# DRV8701EVM_SCHEMATIC.net
KiCad netlist of a schematic drawn in Altium Designer
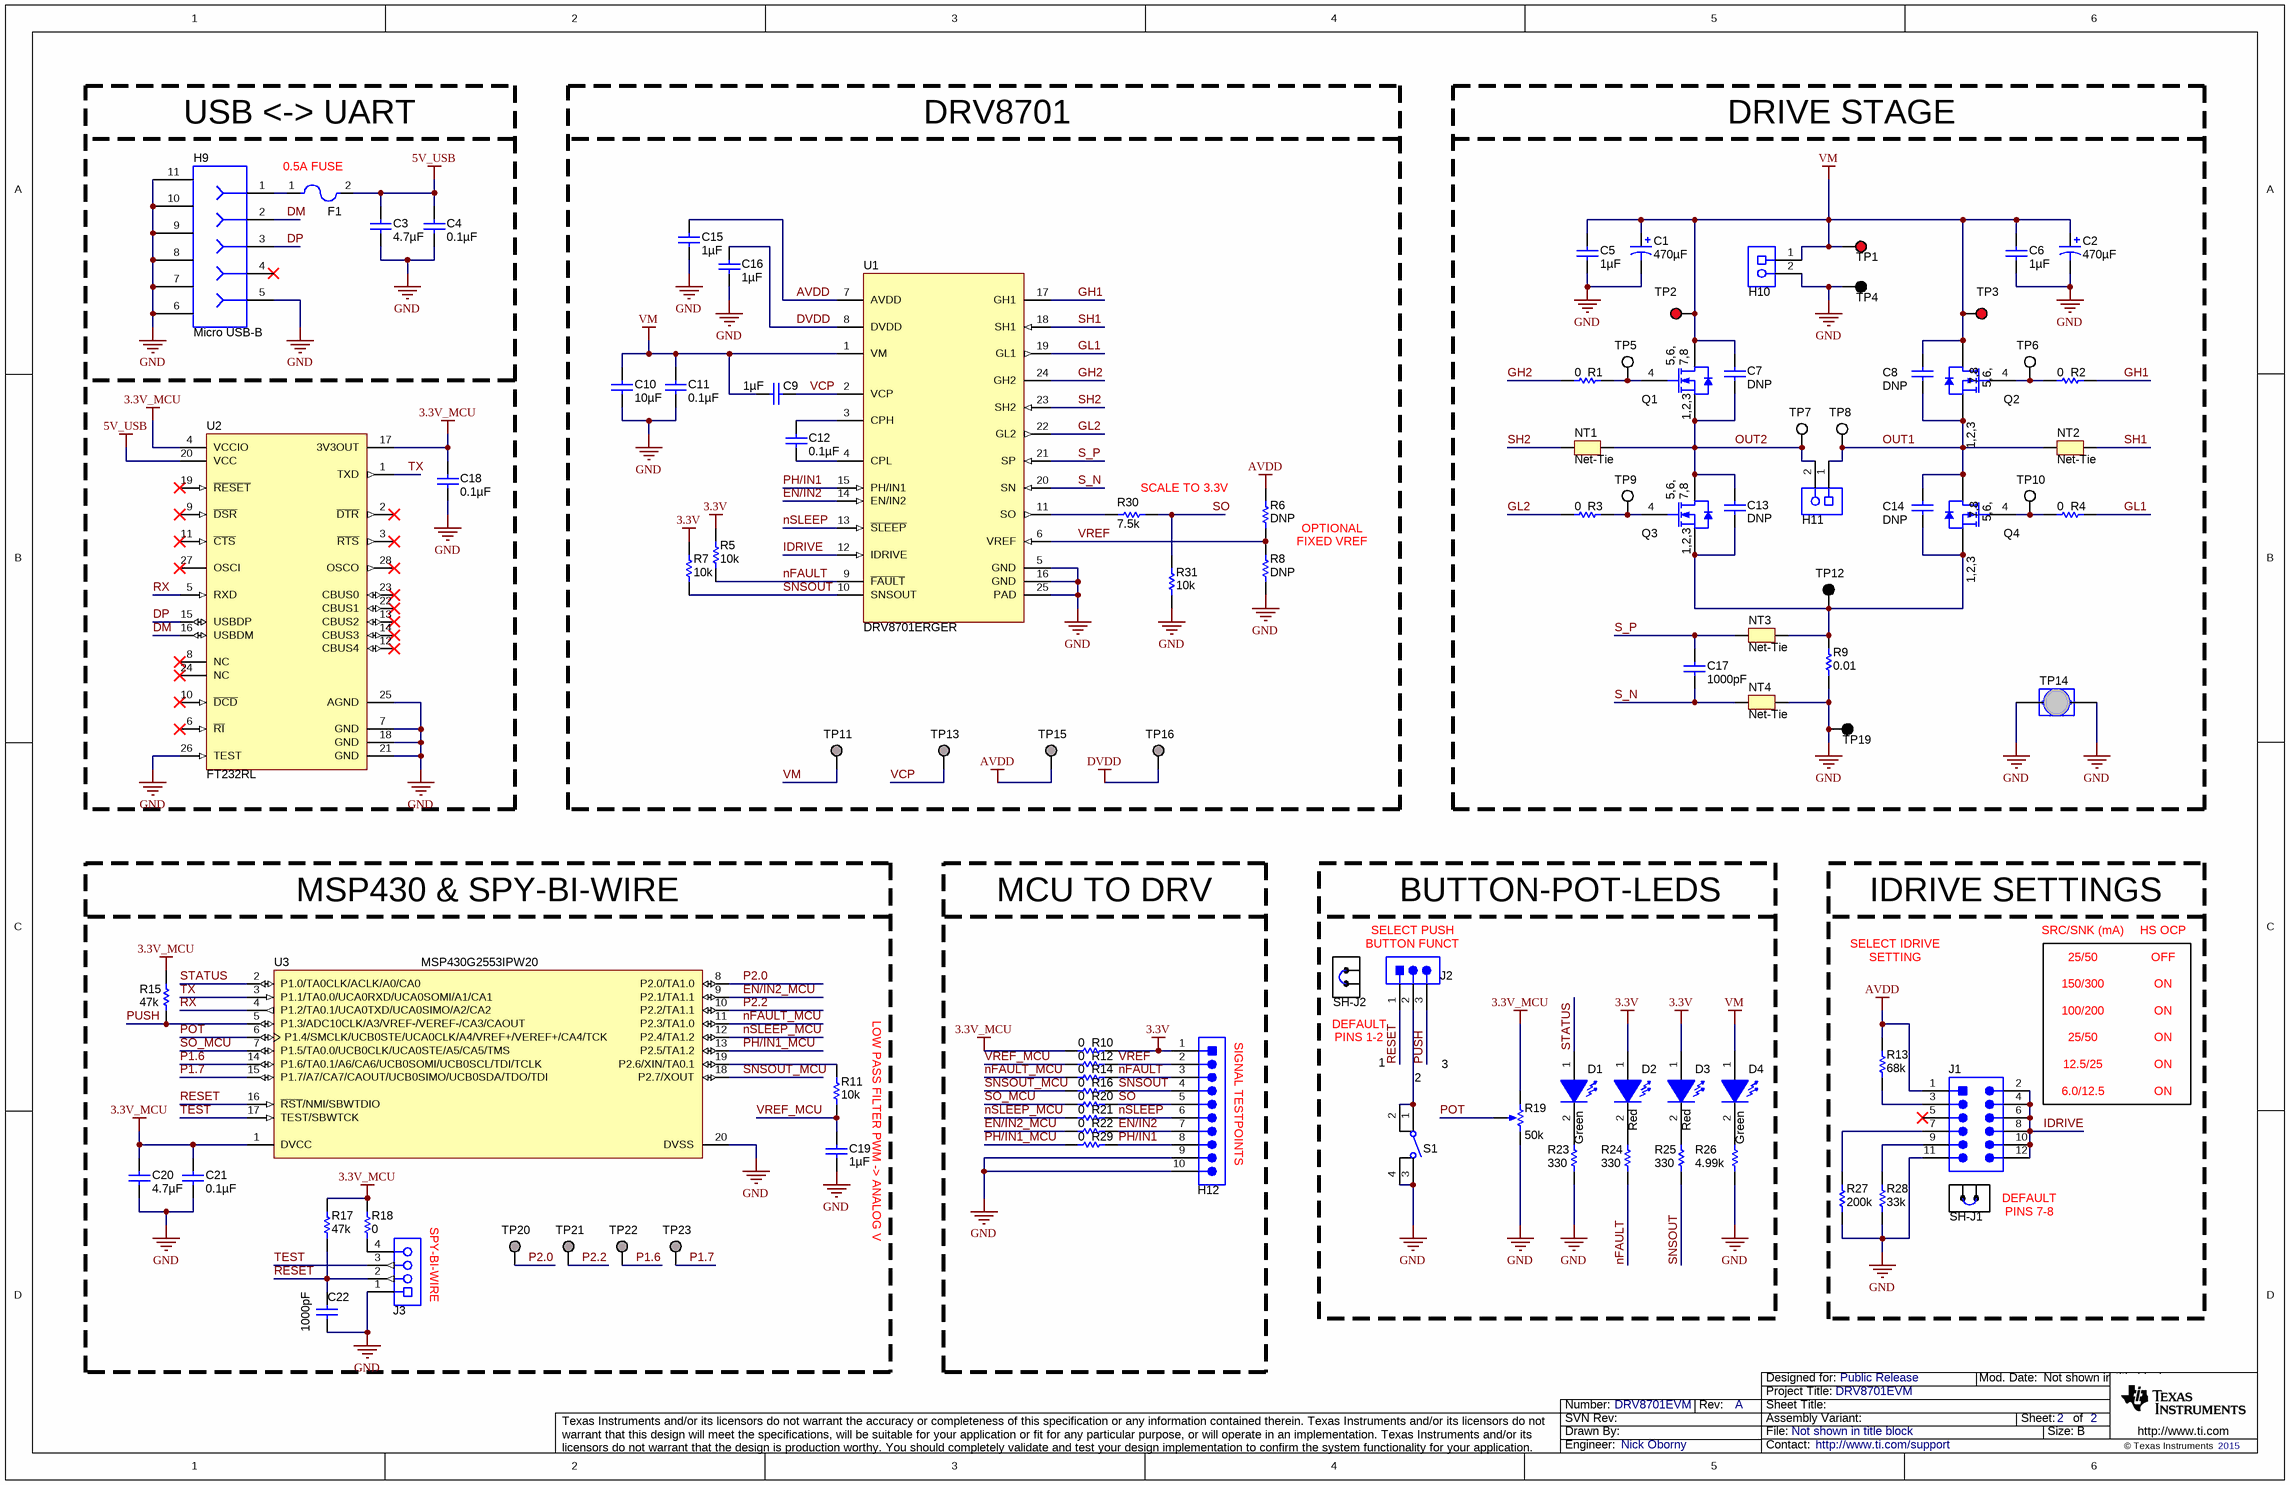
[diagram p0: DRV8701EVM_SCHEMATIC.SchDoc]

(export (version "E")
  (design (tool "Eeschema 10.0.6"))
  (components
    (comp (ref "C1")
      (value "ECA-1HM471")
      (footprint "M_1000x2000")
      (description "CAP, AL, 470 µF, 50 V, +/- 20%,  ohm, TH")
      (fields (field (name "VALUEDISPLAYED") "470µF") (field (name "MANUFACTURER") "Panasonic"))
      (libsource (lib "Capacitor_Aluminum") (part "ECA-1HM471"))
    )
    (comp (ref "C2")
      (value "ECA-1HM471")
      (footprint "M_1000x2000")
      (description "CAP, AL, 470 µF, 50 V, +/- 20%,  ohm, TH")
      (fields (field (name "VALUEDISPLAYED") "470µF") (field (name "MANUFACTURER") "Panasonic"))
      (libsource (lib "Capacitor_Aluminum") (part "ECA-1HM471"))
    )
    (comp (ref "C3")
      (value "C2012X7R1A475M")
      (footprint "0805L")
      (description "CAP, CERM, 4.7uF, 10V, +/-20%, X7R, 0805")
      (fields (field (name "VALUEDISPLAYED") "4.7µF") (field (name "MANUFACTURER") "TDK"))
      (libsource (lib "Capacitor_Ceramic") (part "C2012X7R1A475M"))
    )
    (comp (ref "C4")
      (value "C0603C104K8RACTU")
      (footprint "0603L")
      (description "CAP, CERM, 0.1uF, 10V, +/-10%, X7R, 0603")
      (fields (field (name "VALUEDISPLAYED") "0.1µF") (field (name "MANUFACTURER") "Kemet"))
      (libsource (lib "Capacitor_Ceramic") (part "C0603C104K8RACTU"))
    )
    (comp (ref "C5")
      (value "GRM21BR71H105KA12L")
      (footprint "0805L")
      (description "CAP, CERM, 1uF, 50V, +/-10%, X7R, 0805")
      (fields (field (name "VALUEDISPLAYED") "1µF") (field (name "MANUFACTURER") "MuRata"))
      (libsource (lib "Capacitor_Ceramic") (part "GRM21BR71H105KA12L"))
    )
    (comp (ref "C6")
      (value "GRM21BR71H105KA12L")
      (footprint "0805L")
      (description "CAP, CERM, 1uF, 50V, +/-10%, X7R, 0805")
      (fields (field (name "VALUEDISPLAYED") "1µF") (field (name "MANUFACTURER") "MuRata"))
      (libsource (lib "Capacitor_Ceramic") (part "GRM21BR71H105KA12L"))
    )
    (comp (ref "C7")
      (value "DNP")
      (footprint "0603L")
      (description "CAP, CERM, 0.01uF, 50V, +/-10%, X7R, 0603")
      (fields (field (name "VALUEDISPLAYED") "DNP"))
      (libsource (lib "Capacitor_Ceramic") (part "C1608X7R1H103K"))
    )
    (comp (ref "C8")
      (value "DNP")
      (footprint "0603L")
      (description "CAP, CERM, 0.01uF, 50V, +/-10%, X7R, 0603")
      (fields (field (name "VALUEDISPLAYED") "DNP"))
      (libsource (lib "Capacitor_Ceramic") (part "C1608X7R1H103K"))
    )
    (comp (ref "C9")
      (value "C1608X7R1C105K")
      (footprint "0603L")
      (description "CAP, CERM, 1uF, 16V, +/-10%, X7R, 0603")
      (fields (field (name "VALUEDISPLAYED") "1µF") (field (name "MANUFACTURER") "TDK"))
      (libsource (lib "Capacitor_Ceramic") (part "C1608X7R1C105K"))
    )
    (comp (ref "C10")
      (value "GRM32ER71H106KA12L")
      (footprint "1210L")
      (description "CAP, CERM, 10uF, 50V, +/-10%, X7R, 1210")
      (fields (field (name "VALUEDISPLAYED") "10µF") (field (name "MANUFACTURER") "MuRata"))
      (libsource (lib "Capacitor_Ceramic") (part "GRM32ER71H106KA12L"))
    )
    (comp (ref "C11")
      (value "C1608X7R1H104K")
      (footprint "0603L")
      (description "CAP, CERM, 0.1uF, 50V, +/-10%, X7R, 0603")
      (fields (field (name "VALUEDISPLAYED") "0.1µF") (field (name "MANUFACTURER") "TDK"))
      (libsource (lib "Capacitor_Ceramic") (part "C1608X7R1H104K"))
    )
    (comp (ref "C12")
      (value "C1608X7R1H104K")
      (footprint "0603L")
      (description "CAP, CERM, 0.1uF, 50V, +/-10%, X7R, 0603")
      (fields (field (name "VALUEDISPLAYED") "0.1µF") (field (name "MANUFACTURER") "TDK"))
      (libsource (lib "Capacitor_Ceramic") (part "C1608X7R1H104K"))
    )
    (comp (ref "C13")
      (value "DNP")
      (footprint "0603L")
      (description "CAP, CERM, 0.01uF, 50V, +/-10%, X7R, 0603")
      (fields (field (name "VALUEDISPLAYED") "DNP"))
      (libsource (lib "Capacitor_Ceramic") (part "C1608X7R1H103K"))
    )
    (comp (ref "C14")
      (value "DNP")
      (footprint "0603L")
      (description "CAP, CERM, 0.01uF, 50V, +/-10%, X7R, 0603")
      (fields (field (name "VALUEDISPLAYED") "DNP"))
      (libsource (lib "Capacitor_Ceramic") (part "C1608X7R1H103K"))
    )
    (comp (ref "C15")
      (value "GRM188R70J105KA01D")
      (footprint "0603L")
      (description "CAP, CERM, 1uF, 6.3V, +/-10%, X7R, 0603")
      (fields (field (name "VALUEDISPLAYED") "1µF") (field (name "MANUFACTURER") "MuRata"))
      (libsource (lib "Capacitor_Ceramic") (part "GRM188R70J105KA01D"))
    )
    (comp (ref "C16")
      (value "GRM188R70J105KA01D")
      (footprint "0603L")
      (description "CAP, CERM, 1uF, 6.3V, +/-10%, X7R, 0603")
      (fields (field (name "VALUEDISPLAYED") "1µF") (field (name "MANUFACTURER") "MuRata"))
      (libsource (lib "Capacitor_Ceramic") (part "GRM188R70J105KA01D"))
    )
    (comp (ref "C17")
      (value "GRM155R71C102KA01D")
      (footprint "0402L")
      (description "CAP, CERM, 1000pF, 16V, +/-10%, X7R, 0402")
      (fields (field (name "VALUEDISPLAYED") "1000pF") (field (name "MANUFACTURER") "MuRata"))
      (libsource (lib "Capacitor_Ceramic") (part "GRM155R71C102KA01D"))
    )
    (comp (ref "C18")
      (value "C0603C104K8RACTU")
      (footprint "0603L")
      (description "CAP, CERM, 0.1uF, 10V, +/-10%, X7R, 0603")
      (fields (field (name "VALUEDISPLAYED") "0.1µF") (field (name "MANUFACTURER") "Kemet"))
      (libsource (lib "Capacitor_Ceramic") (part "C0603C104K8RACTU"))
    )
    (comp (ref "C19")
      (value "GRM188R70J105KA01D")
      (footprint "0603L")
      (description "CAP, CERM, 1uF, 6.3V, +/-10%, X7R, 0603")
      (fields (field (name "VALUEDISPLAYED") "1µF") (field (name "MANUFACTURER") "MuRata"))
      (libsource (lib "Capacitor_Ceramic") (part "GRM188R70J105KA01D"))
    )
    (comp (ref "C20")
      (value "C2012X7R1A475M")
      (footprint "0805L")
      (description "CAP, CERM, 4.7uF, 10V, +/-20%, X7R, 0805")
      (fields (field (name "VALUEDISPLAYED") "4.7µF") (field (name "MANUFACTURER") "TDK"))
      (libsource (lib "Capacitor_Ceramic") (part "C2012X7R1A475M"))
    )
    (comp (ref "C21")
      (value "C0603C104K8RACTU")
      (footprint "0603L")
      (description "CAP, CERM, 0.1uF, 10V, +/-10%, X7R, 0603")
      (fields (field (name "VALUEDISPLAYED") "0.1µF") (field (name "MANUFACTURER") "Kemet"))
      (libsource (lib "Capacitor_Ceramic") (part "C0603C104K8RACTU"))
    )
    (comp (ref "C22")
      (value "GRM188R71C102KA01D")
      (footprint "0603L")
      (description "CAP, CERM, 1000pF, 16V, +/-10%, X7R, 0603")
      (fields (field (name "VALUEDISPLAYED") "1000pF") (field (name "MANUFACTURER") "MuRata"))
      (libsource (lib "Capacitor_Ceramic") (part "GRM188R71C102KA01D"))
    )
    (comp (ref "D1")
      (value "Green")
      (footprint "LED_LTST-C171")
      (description "LED, Green, SMD")
      (fields (field (name "MANUFACTURER") "Lite-On") (field (name "PARTNUMBER") "LTST-C171GKT"))
      (libsource (lib "LED") (part "LTST-C171GKT"))
    )
    (comp (ref "D2")
      (value "Red")
      (footprint "LED_LTST-C170")
      (description "LED, Red, SMD")
      (fields (field (name "MANUFACTURER") "Lite-On") (field (name "PARTNUMBER") "LTST-C170KRKT"))
      (libsource (lib "LED") (part "LTST-C170KRKT"))
    )
    (comp (ref "D3")
      (value "Red")
      (footprint "LED_LTST-C170")
      (description "LED, Red, SMD")
      (fields (field (name "MANUFACTURER") "Lite-On") (field (name "PARTNUMBER") "LTST-C170KRKT"))
      (libsource (lib "LED") (part "LTST-C170KRKT"))
    )
    (comp (ref "D4")
      (value "Green")
      (footprint "LED_LTST-C171")
      (description "LED, Green, SMD")
      (fields (field (name "MANUFACTURER") "Lite-On") (field (name "PARTNUMBER") "LTST-C171GKT"))
      (libsource (lib "LED") (part "LTST-C171GKT"))
    )
    (comp (ref "F1")
      (value "1206L050/15YR")
      (footprint "1206_FUSE")
      (description "Fuse, Poly Resetable PTC, 0.5A")
      (fields (field (name "MANUFACTURER") "Littelfuse"))
      (libsource (lib "PADSlegacy_Passive") (part "FUSE_1206L_SERIES"))
    )
    (comp (ref "H9")
      (value "ZX62-B-5PA(11)")
      (footprint "CONN_USB_micro_ZX62-B-5PA")
      (description "Connector, micro USB Type B, Receptacle, R/A, SMD")
      (fields
        (field (name "MANUFACTURER") "Hirose Electric Co. Ltd.")
        (field (name "PACKAGEREFERENCE") "Micro USB-B")
      )
      (libsource (lib "Connectors") (part "ZX62-B-5PA(11)"))
    )
    (comp (ref "H10")
      (value "691 101 710 002")
      (footprint "Wurth_691101710002")
      (description "Terminal Block, 5 mm, 2x1, Tin, TH")
      (fields (field (name "MANUFACTURER") "Wurth Elektronik eiSos"))
      (libsource (lib "Connectors_Other") (part "691 101 710 002"))
    )
    (comp (ref "H11")
      (value "691 101 710 002")
      (footprint "Wurth_691101710002")
      (description "Terminal Block, 5 mm, 2x1, Tin, TH")
      (fields (field (name "MANUFACTURER") "Wurth Elektronik eiSos"))
      (libsource (lib "Connectors_Other") (part "691 101 710 002"))
    )
    (comp (ref "H12")
      (value "TSW-110-07-G-S")
      (footprint "TSW-110-07-G-S")
      (description "Header, 100mil, 10x1, Gold, TH")
      (fields (field (name "MANUFACTURER") "Samtec"))
      (libsource (lib "Connectors_Samtec") (part "TSW-110-07-G-S"))
    )
    (comp (ref "J1")
      (value "PEC06DAAN")
      (footprint "CONN_PEC06DAAN")
      (description "Header, 100mil, 6x2, Tin, TH")
      (fields (field (name "MANUFACTURER") "Sullins Connector Solutions"))
      (libsource (lib "Connectors_Sullins") (part "PEC06DAAN"))
    )
    (comp (ref "J2")
      (value "PEC03SAAN")
      (footprint "CONN_PEC03SAAN")
      (description "Header, 100mil, 3x1, Tin, TH")
      (fields (field (name "MANUFACTURER") "Sullins Connector Solutions"))
      (libsource (lib "Connectors_Sullins") (part "PEC03SAAN"))
    )
    (comp (ref "J3")
      (value "851-43-004-20-001000")
      (footprint "CONN_851-43-004-20-001000")
      (description "SOCKET .050\" GRID SIP 4 POS R/A, TH")
      (fields (field (name "MANUFACTURER") "Mill-Max"))
      (libsource (lib "Connectors") (part "851-43-004-20-001000"))
    )
    (comp (ref "NT1")
      (value "Net-Tie")
      (footprint "Net-Tie_10mil")
      (description "Single point connection between nets.")
      (libsource (lib "") (part "Net-Tie_1"))
    )
    (comp (ref "NT2")
      (value "Net-Tie")
      (footprint "Net-Tie_10mil")
      (description "Single point connection between nets.")
      (libsource (lib "MiscParts") (part "Net-Tie"))
    )
    (comp (ref "NT3")
      (value "Net-Tie")
      (footprint "Net-Tie_10mil")
      (description "Single point connection between nets.")
      (libsource (lib "MiscParts") (part "Net-Tie"))
    )
    (comp (ref "NT4")
      (value "Net-Tie")
      (footprint "Net-Tie_10mil")
      (description "Single point connection between nets.")
      (libsource (lib "") (part "Net-Tie_1"))
    )
    (comp (ref "Q1")
      (value "CSD18532Q5B")
      (footprint "TRANS_NexFET_Q5B")
      (description "MOSFET, N-CH, 60V, 172A, SON 5x6mm")
      (fields (field (name "MANUFACTURER") "Texas Instruments"))
      (libsource (lib "FETs") (part "CSD18532Q5B"))
    )
    (comp (ref "Q2")
      (value "CSD18532Q5B")
      (footprint "TRANS_NexFET_Q5B")
      (description "MOSFET, N-CH, 60V, 172A, SON 5x6mm")
      (fields (field (name "MANUFACTURER") "Texas Instruments"))
      (libsource (lib "FETs") (part "CSD18532Q5B"))
    )
    (comp (ref "Q3")
      (value "CSD18532Q5B")
      (footprint "TRANS_NexFET_Q5B")
      (description "MOSFET, N-CH, 60V, 172A, SON 5x6mm")
      (fields (field (name "MANUFACTURER") "Texas Instruments"))
      (libsource (lib "FETs") (part "CSD18532Q5B"))
    )
    (comp (ref "Q4")
      (value "CSD18532Q5B")
      (footprint "TRANS_NexFET_Q5B")
      (description "MOSFET, N-CH, 60V, 172A, SON 5x6mm")
      (fields (field (name "MANUFACTURER") "Texas Instruments"))
      (libsource (lib "FETs") (part "CSD18532Q5B"))
    )
    (comp (ref "R1")
      (value "0")
      (footprint "0603L")
      (description "RES, 0 ohm, 5%, 0.1W, 0603")
      (fields (field (name "PARTNUMBER") "CRCW06030000Z0EA") (field (name "MANUFACTURER") "Vishay-Dale"))
      (libsource (lib "Resistor_0603") (part "CRCW06030000Z0EA"))
    )
    (comp (ref "R2")
      (value "0")
      (footprint "0603L")
      (description "RES, 0 ohm, 5%, 0.1W, 0603")
      (fields (field (name "PARTNUMBER") "CRCW06030000Z0EA") (field (name "MANUFACTURER") "Vishay-Dale"))
      (libsource (lib "Resistor_0603") (part "CRCW06030000Z0EA"))
    )
    (comp (ref "R3")
      (value "0")
      (footprint "0603L")
      (description "RES, 0 ohm, 5%, 0.1W, 0603")
      (fields (field (name "PARTNUMBER") "CRCW06030000Z0EA") (field (name "MANUFACTURER") "Vishay-Dale"))
      (libsource (lib "Resistor_0603") (part "CRCW06030000Z0EA"))
    )
    (comp (ref "R4")
      (value "0")
      (footprint "0603L")
      (description "RES, 0 ohm, 5%, 0.1W, 0603")
      (fields (field (name "PARTNUMBER") "CRCW06030000Z0EA") (field (name "MANUFACTURER") "Vishay-Dale"))
      (libsource (lib "Resistor_0603") (part "CRCW06030000Z0EA"))
    )
    (comp (ref "R5")
      (value "10k")
      (footprint "0603L")
      (description "RES, 10k ohm, 5%, 0.1W, 0603")
      (fields (field (name "PARTNUMBER") "CRCW060310K0JNEA") (field (name "MANUFACTURER") "Vishay-Dale"))
      (libsource (lib "Resistor_0603") (part "CRCW060310K0JNEA"))
    )
    (comp (ref "R6")
      (value "DNP")
      (footprint "0603L")
      (description "RES, 0 ohm, 5%, 0.1W, 0603")
      (libsource (lib "Resistor_0603") (part "CRCW06030000Z0EA"))
    )
    (comp (ref "R7")
      (value "10k")
      (footprint "0603L")
      (description "RES, 10k ohm, 5%, 0.1W, 0603")
      (fields (field (name "PARTNUMBER") "CRCW060310K0JNEA") (field (name "MANUFACTURER") "Vishay-Dale"))
      (libsource (lib "Resistor_0603") (part "CRCW060310K0JNEA"))
    )
    (comp (ref "R8")
      (value "DNP")
      (footprint "0603L")
      (description "RES, 0 ohm, 5%, 0.1W, 0603")
      (libsource (lib "Resistor_0603") (part "CRCW06030000Z0EA"))
    )
    (comp (ref "R9")
      (value "0.01")
      (footprint "2512M")
      (description "RES, 0.01 ohm, 1%, 3W, 2512")
      (fields (field (name "PARTNUMBER") "CRA2512-FZ-R010ELF") (field (name "MANUFACTURER") "Bourns"))
      (libsource (lib "Resistor_OtherSMT") (part "CRA2512-FZ-R010ELF"))
    )
    (comp (ref "R10")
      (value "0")
      (footprint "0603L")
      (description "RES, 0 ohm, 5%, 0.1W, 0603")
      (fields (field (name "PARTNUMBER") "CRCW06030000Z0EA") (field (name "MANUFACTURER") "Vishay-Dale"))
      (libsource (lib "Resistor_0603") (part "CRCW06030000Z0EA"))
    )
    (comp (ref "R11")
      (value "10k")
      (footprint "0603L")
      (description "RES, 10k ohm, 5%, 0.1W, 0603")
      (fields (field (name "PARTNUMBER") "CRCW060310K0JNEA") (field (name "MANUFACTURER") "Vishay-Dale"))
      (libsource (lib "Resistor_0603") (part "CRCW060310K0JNEA"))
    )
    (comp (ref "R12")
      (value "0")
      (footprint "0603L")
      (description "RES, 0 ohm, 5%, 0.1W, 0603")
      (fields (field (name "PARTNUMBER") "CRCW06030000Z0EA") (field (name "MANUFACTURER") "Vishay-Dale"))
      (libsource (lib "Resistor_0603") (part "CRCW06030000Z0EA"))
    )
    (comp (ref "R13")
      (value "68k")
      (footprint "0603L")
      (description "RES, 68k ohm, 5%, 0.1W, 0603")
      (fields (field (name "PARTNUMBER") "CRCW060368K0JNEA") (field (name "MANUFACTURER") "Vishay-Dale"))
      (libsource (lib "Resistor_0603") (part "CRCW060368K0JNEA"))
    )
    (comp (ref "R14")
      (value "0")
      (footprint "0603L")
      (description "RES, 0 ohm, 5%, 0.1W, 0603")
      (fields (field (name "PARTNUMBER") "CRCW06030000Z0EA") (field (name "MANUFACTURER") "Vishay-Dale"))
      (libsource (lib "Resistor_0603") (part "CRCW06030000Z0EA"))
    )
    (comp (ref "R15")
      (value "47k")
      (footprint "0603L")
      (description "RES, 47k ohm, 5%, 0.1W, 0603")
      (fields (field (name "PARTNUMBER") "CRCW060347K0JNEA") (field (name "MANUFACTURER") "Vishay-Dale"))
      (libsource (lib "Resistor_0603") (part "CRCW060347K0JNEA"))
    )
    (comp (ref "R16")
      (value "0")
      (footprint "0603L")
      (description "RES, 0 ohm, 5%, 0.1W, 0603")
      (fields (field (name "PARTNUMBER") "CRCW06030000Z0EA") (field (name "MANUFACTURER") "Vishay-Dale"))
      (libsource (lib "Resistor_0603") (part "CRCW06030000Z0EA"))
    )
    (comp (ref "R17")
      (value "47k")
      (footprint "0603L")
      (description "RES, 47k ohm, 5%, 0.1W, 0603")
      (fields (field (name "PARTNUMBER") "CRCW060347K0JNEA") (field (name "MANUFACTURER") "Vishay-Dale"))
      (libsource (lib "Resistor_0603") (part "CRCW060347K0JNEA"))
    )
    (comp (ref "R18")
      (value "0")
      (footprint "0603L")
      (description "RES, 0 ohm, 5%, 0.1W, 0603")
      (fields (field (name "PARTNUMBER") "CRCW06030000Z0EA") (field (name "MANUFACTURER") "Vishay-Dale"))
      (libsource (lib "Resistor_0603") (part "CRCW06030000Z0EA"))
    )
    (comp (ref "R19")
      (value "50k")
      (footprint "Bourns_3352T")
      (description "Trimming Potentiometer, 50K, 0.5W, TH")
      (fields (field (name "PARTNUMBER") "3352T-1-503LF") (field (name "MANUFACTURER") "Bourns"))
      (libsource (lib "Other_Passive") (part "3352T-1-503LF"))
    )
    (comp (ref "R20")
      (value "0")
      (footprint "0603L")
      (description "RES, 0 ohm, 5%, 0.1W, 0603")
      (fields (field (name "PARTNUMBER") "CRCW06030000Z0EA") (field (name "MANUFACTURER") "Vishay-Dale"))
      (libsource (lib "Resistor_0603") (part "CRCW06030000Z0EA"))
    )
    (comp (ref "R21")
      (value "0")
      (footprint "0603L")
      (description "RES, 0 ohm, 5%, 0.1W, 0603")
      (fields (field (name "PARTNUMBER") "CRCW06030000Z0EA") (field (name "MANUFACTURER") "Vishay-Dale"))
      (libsource (lib "Resistor_0603") (part "CRCW06030000Z0EA"))
    )
    (comp (ref "R22")
      (value "0")
      (footprint "0603L")
      (description "RES, 0 ohm, 5%, 0.1W, 0603")
      (fields (field (name "PARTNUMBER") "CRCW06030000Z0EA") (field (name "MANUFACTURER") "Vishay-Dale"))
      (libsource (lib "Resistor_0603") (part "CRCW06030000Z0EA"))
    )
    (comp (ref "R23")
      (value "330")
      (footprint "0603L")
      (description "RES, 330 ohm, 5%, 0.1W, 0603")
      (fields (field (name "PARTNUMBER") "CRCW0603330RJNEA") (field (name "MANUFACTURER") "Vishay-Dale"))
      (libsource (lib "Resistor_0603") (part "CRCW0603330RJNEA"))
    )
    (comp (ref "R24")
      (value "330")
      (footprint "0603L")
      (description "RES, 330 ohm, 5%, 0.1W, 0603")
      (fields (field (name "PARTNUMBER") "CRCW0603330RJNEA") (field (name "MANUFACTURER") "Vishay-Dale"))
      (libsource (lib "Resistor_0603") (part "CRCW0603330RJNEA"))
    )
    (comp (ref "R25")
      (value "330")
      (footprint "0603L")
      (description "RES, 330 ohm, 5%, 0.1W, 0603")
      (fields (field (name "PARTNUMBER") "CRCW0603330RJNEA") (field (name "MANUFACTURER") "Vishay-Dale"))
      (libsource (lib "Resistor_0603") (part "CRCW0603330RJNEA"))
    )
    (comp (ref "R26")
      (value "4.99k")
      (footprint "0603L")
      (description "RES, 4.99k ohm, 1%, 0.1W, 0603")
      (fields (field (name "PARTNUMBER") "CRCW06034K99FKEA") (field (name "MANUFACTURER") "Vishay-Dale"))
      (libsource (lib "Resistor_0603") (part "CRCW06034K99FKEA"))
    )
    (comp (ref "R27")
      (value "200k")
      (footprint "0603L")
      (description "RES, 200k ohm, 5%, 0.1W, 0603")
      (fields (field (name "PARTNUMBER") "CRCW0603200KJNEA") (field (name "MANUFACTURER") "Vishay-Dale"))
      (libsource (lib "Resistor_0603") (part "CRCW0603200KJNEA"))
    )
    (comp (ref "R28")
      (value "33k")
      (footprint "0603L")
      (description "RES, 33k ohm, 5%, 0.1W, 0603")
      (fields (field (name "PARTNUMBER") "CRCW060333K0JNEA") (field (name "MANUFACTURER") "Vishay-Dale"))
      (libsource (lib "Resistor_0603") (part "CRCW060333K0JNEA"))
    )
    (comp (ref "R29")
      (value "0")
      (footprint "0603L")
      (description "RES, 0 ohm, 5%, 0.1W, 0603")
      (fields (field (name "PARTNUMBER") "CRCW06030000Z0EA") (field (name "MANUFACTURER") "Vishay-Dale"))
      (libsource (lib "Resistor_0603") (part "CRCW06030000Z0EA"))
    )
    (comp (ref "R30")
      (value "CRCW06037K50JNEA")
      (footprint "0603L")
      (description "RES, 7.5 k, 5%, 0.1 W, 0603")
      (fields (field (name "VALUEDISPLAYED") "7.5k") (field (name "MANUFACTURER") "Vishay-Dale"))
      (libsource (lib "Resistor_0603") (part "CRCW06037K50JNEA"))
    )
    (comp (ref "R31")
      (value "CRCW060310K0JNEA")
      (footprint "0603L")
      (description "RES, 10 k, 5%, 0.1 W, 0603")
      (fields (field (name "VALUEDISPLAYED") "10k") (field (name "MANUFACTURER") "Vishay-Dale"))
      (libsource (lib "Resistor_0603") (part "CRCW060310K0JNEA"))
    )
    (comp (ref "S1")
      (value "4-1437565-1")
      (footprint "SW_FSM4JSMA")
      (description "Switch, Tactile, SPST-NO, 0.05A, 12V, SMT")
      (fields (field (name "MANUFACTURER") "TE Connectivity"))
      (libsource (lib "Switches") (part "4-1437565-1"))
    )
    (comp (ref "SH-J1")
      (value "969102-0000-DA")
      (footprint "SNT-100-BK-G")
      (description "Shunt, 100mil, Gold plated, Black")
      (fields (field (name "MANUFACTURER") "3M") (field (name "ALTERNATE PARTNUMBER") "SNT-100-BK-G"))
      (libsource (lib "Hardware") (part "969102-0000-DA"))
    )
    (comp (ref "SH-J2")
      (value "969102-0000-DA")
      (footprint "SNT-100-BK-G")
      (description "Shunt, 100mil, Gold plated, Black")
      (fields (field (name "MANUFACTURER") "3M") (field (name "ALTERNATE PARTNUMBER") "SNT-100-BK-G"))
      (libsource (lib "") (part "969102-0000-DA_1"))
    )
    (comp (ref "TP1")
      (value "5005")
      (footprint "Keystone5005")
      (description "Test Point, Compact, Red, TH")
      (fields (field (name "MANUFACTURER") "Keystone"))
      (libsource (lib "Connectors") (part "5005"))
    )
    (comp (ref "TP2")
      (value "5005")
      (footprint "Keystone5005")
      (description "Test Point, Compact, Red, TH")
      (fields (field (name "MANUFACTURER") "Keystone"))
      (libsource (lib "Connectors") (part "5005"))
    )
    (comp (ref "TP3")
      (value "5005")
      (footprint "Keystone5005")
      (description "Test Point, Compact, Red, TH")
      (fields (field (name "MANUFACTURER") "Keystone"))
      (libsource (lib "Connectors") (part "5005"))
    )
    (comp (ref "TP4")
      (value "5006")
      (footprint "Keystone5006")
      (description "Test Point, Compact, Black, TH")
      (fields (field (name "MANUFACTURER") "Keystone"))
      (libsource (lib "Connectors") (part "5006"))
    )
    (comp (ref "TP5")
      (value "5007")
      (footprint "Keystone5007")
      (description "Test Point, Compact, White, TH")
      (fields (field (name "MANUFACTURER") "Keystone"))
      (libsource (lib "Connectors") (part "5007"))
    )
    (comp (ref "TP6")
      (value "5007")
      (footprint "Keystone5007")
      (description "Test Point, Compact, White, TH")
      (fields (field (name "MANUFACTURER") "Keystone"))
      (libsource (lib "Connectors") (part "5007"))
    )
    (comp (ref "TP7")
      (value "5007")
      (footprint "Keystone5007")
      (description "Test Point, Compact, White, TH")
      (fields (field (name "MANUFACTURER") "Keystone"))
      (libsource (lib "Connectors") (part "5007"))
    )
    (comp (ref "TP8")
      (value "5007")
      (footprint "Keystone5007")
      (description "Test Point, Compact, White, TH")
      (fields (field (name "MANUFACTURER") "Keystone"))
      (libsource (lib "Connectors") (part "5007"))
    )
    (comp (ref "TP9")
      (value "5007")
      (footprint "Keystone5007")
      (description "Test Point, Compact, White, TH")
      (fields (field (name "MANUFACTURER") "Keystone"))
      (libsource (lib "Connectors") (part "5007"))
    )
    (comp (ref "TP10")
      (value "5007")
      (footprint "Keystone5007")
      (description "Test Point, Compact, White, TH")
      (fields (field (name "MANUFACTURER") "Keystone"))
      (libsource (lib "Connectors") (part "5007"))
    )
    (comp (ref "TP11")
      (value "VM")
      (footprint "TP_VIA_018RND008")
      (description "TEST POINT.  No entry in BOM.")
      (libsource (lib "MiscParts") (part "TESTPOINT"))
    )
    (comp (ref "TP12")
      (value "5006")
      (footprint "Keystone5006")
      (description "Test Point, Compact, Black, TH")
      (fields (field (name "MANUFACTURER") "Keystone"))
      (libsource (lib "Connectors") (part "5006"))
    )
    (comp (ref "TP13")
      (value "VCP")
      (footprint "TP_VIA_018RND008")
      (description "TEST POINT.  No entry in BOM.")
      (libsource (lib "MiscParts") (part "TESTPOINT"))
    )
    (comp (ref "TP14")
      (value "D3082-05")
      (footprint "Harwin_D3082-05")
      (description "1mm Uninsulated Shorting Plug, 10.16mm spacing, TH")
      (fields (field (name "MANUFACTURER") "Harwin"))
      (libsource (lib "Connectors_Other") (part "D3082-05"))
    )
    (comp (ref "TP15")
      (value "AVDD")
      (footprint "TP_VIA_018RND008")
      (description "TEST POINT.  No entry in BOM.")
      (libsource (lib "MiscParts") (part "TESTPOINT"))
    )
    (comp (ref "TP16")
      (value "DVDD")
      (footprint "TP_VIA_018RND008")
      (description "TEST POINT.  No entry in BOM.")
      (libsource (lib "MiscParts") (part "TESTPOINT"))
    )
    (comp (ref "TP19")
      (value "5006")
      (footprint "Keystone5006")
      (description "Test Point, Compact, Black, TH")
      (fields (field (name "MANUFACTURER") "Keystone"))
      (libsource (lib "Connectors") (part "5006"))
    )
    (comp (ref "TP20")
      (value "TESTPOINT")
      (footprint "TP_VIA_060RND040")
      (description "TEST POINT.  No entry in BOM.")
      (libsource (lib "MiscParts") (part "TESTPOINT"))
    )
    (comp (ref "TP21")
      (value "TESTPOINT")
      (footprint "TP_VIA_060RND040")
      (description "TEST POINT.  No entry in BOM.")
      (libsource (lib "MiscParts") (part "TESTPOINT"))
    )
    (comp (ref "TP22")
      (value "TESTPOINT")
      (footprint "TP_VIA_060RND040")
      (description "TEST POINT.  No entry in BOM.")
      (libsource (lib "MiscParts") (part "TESTPOINT"))
    )
    (comp (ref "TP23")
      (value "TESTPOINT")
      (footprint "TP_VIA_060RND040")
      (description "TEST POINT.  No entry in BOM.")
      (libsource (lib "MiscParts") (part "TESTPOINT"))
    )
    (comp (ref "U1")
      (value "DRV8701ERGER")
      (footprint "RGE0024F")
      (description "H-Bridge Gate Driver, RGE0024F")
      (fields
        (field (name "ALTERNATE PARTNUMBER") "DRV8701ERGET")
        (field (name "MANUFACTURER") "Texas Instruments")
      )
      (libsource (lib "TI_Pre_RTM") (part "DRV8701ERGER"))
    )
    (comp (ref "U2")
      (value "FT232RL")
      (footprint "SSOP28_N")
      (description "USB to Serial UART, SSOP28")
      (fields (field (name "MANUFACTURER") "FTDI"))
      (libsource (lib "Other_IC") (part "FT232RL"))
    )
    (comp (ref "U3")
      (value "MSP430G2553IPW20")
      (footprint "PW0020A_N")
      (fields
        (field (name "ALTERNATE PARTNUMBER") "Equivalent")
        (field (name "MANUFACTURER") "Texas Instruments")
      )
      (libsource (lib "TI MCU MSP430") (part "MSP430G2553IPW20"))
    )
  )
  (nets
    (net (code "1") (name "/DM") (class "Default")
      (node (ref "H9") (pin "2") (pinfunction "2_2") (pintype "passive"))
      (node (ref "U2") (pin "16") (pinfunction "USBDM_16") (pintype "bidirectional"))
    )
    (net (code "2") (name "/DP") (class "Default")
      (node (ref "H9") (pin "3") (pinfunction "3_3") (pintype "passive"))
      (node (ref "U2") (pin "15") (pinfunction "USBDP_15") (pintype "bidirectional"))
    )
    (net (code "3") (name "/EN{slash}IN2") (class "Default")
      (node (ref "H12") (pin "7") (pinfunction "7_7") (pintype "passive"))
      (node (ref "R22") (pin "1") (pinfunction "1_1") (pintype "passive"))
      (node (ref "U1") (pin "14") (pinfunction "EN/IN2_14") (pintype "input"))
    )
    (net (code "4") (name "/EN{slash}IN2_MCU") (class "Default")
      (node (ref "R22") (pin "2") (pinfunction "2_2") (pintype "passive"))
      (node (ref "U3") (pin "9") (pinfunction "P2.1/TA1.1_9") (pintype "bidirectional"))
    )
    (net (code "5") (name "/GH1") (class "Default")
      (node (ref "R2") (pin "1") (pinfunction "1_1") (pintype "passive"))
      (node (ref "U1") (pin "17") (pinfunction "GH1_17") (pintype "power_in"))
    )
    (net (code "6") (name "/GH2") (class "Default")
      (node (ref "R1") (pin "2") (pinfunction "2_2") (pintype "passive"))
      (node (ref "U1") (pin "24") (pinfunction "GH2_24") (pintype "power_in"))
    )
    (net (code "7") (name "/GL1") (class "Default")
      (node (ref "R4") (pin "1") (pinfunction "1_1") (pintype "passive"))
      (node (ref "U1") (pin "19") (pinfunction "GL1_19") (pintype "output"))
    )
    (net (code "8") (name "/GL2") (class "Default")
      (node (ref "R3") (pin "2") (pinfunction "2_2") (pintype "passive"))
      (node (ref "U1") (pin "22") (pinfunction "GL2_22") (pintype "output"))
    )
    (net (code "9") (name "/IDRIVE") (class "Default")
      (node (ref "J1") (pin "10") (pinfunction "10_10") (pintype "passive"))
      (node (ref "J1") (pin "12") (pinfunction "12_12") (pintype "passive"))
      (node (ref "J1") (pin "2") (pinfunction "2_2") (pintype "passive"))
      (node (ref "J1") (pin "4") (pinfunction "4_4") (pintype "passive"))
      (node (ref "J1") (pin "6") (pinfunction "6_6") (pintype "passive"))
      (node (ref "J1") (pin "8") (pinfunction "8_8") (pintype "passive"))
      (node (ref "U1") (pin "12") (pinfunction "IDRIVE_12") (pintype "input"))
    )
    (net (code "10") (name "/OUT1") (class "Default")
      (node (ref "C14") (pin "1") (pinfunction "1_1") (pintype "passive"))
      (node (ref "C8") (pin "2") (pinfunction "2_2") (pintype "passive"))
      (node (ref "H11") (pin "1") (pinfunction "1_1") (pintype "passive"))
      (node (ref "NT2") (pin "2") (pinfunction "2_2") (pintype "passive"))
      (node (ref "Q2") (pin "1") (pinfunction "S_1") (pintype "passive"))
      (node (ref "Q2") (pin "2") (pinfunction "S_2") (pintype "passive"))
      (node (ref "Q2") (pin "3") (pinfunction "S_3") (pintype "passive"))
      (node (ref "Q4") (pin "5") (pinfunction "D_5") (pintype "passive"))
      (node (ref "Q4") (pin "6") (pinfunction "D_6") (pintype "passive"))
      (node (ref "Q4") (pin "7") (pinfunction "D_7") (pintype "passive"))
      (node (ref "Q4") (pin "8") (pinfunction "D_8") (pintype "passive"))
      (node (ref "TP8") (pin "1") (pintype "passive"))
    )
    (net (code "11") (name "/OUT2") (class "Default")
      (node (ref "C13") (pin "1") (pinfunction "1_1") (pintype "passive"))
      (node (ref "C7") (pin "2") (pinfunction "2_2") (pintype "passive"))
      (node (ref "H11") (pin "2") (pinfunction "2_2") (pintype "passive"))
      (node (ref "NT1") (pin "2") (pinfunction "2_2") (pintype "passive"))
      (node (ref "Q1") (pin "1") (pinfunction "S_1") (pintype "passive"))
      (node (ref "Q1") (pin "2") (pinfunction "S_2") (pintype "passive"))
      (node (ref "Q1") (pin "3") (pinfunction "S_3") (pintype "passive"))
      (node (ref "Q3") (pin "5") (pinfunction "D_5") (pintype "passive"))
      (node (ref "Q3") (pin "6") (pinfunction "D_6") (pintype "passive"))
      (node (ref "Q3") (pin "7") (pinfunction "D_7") (pintype "passive"))
      (node (ref "Q3") (pin "8") (pinfunction "D_8") (pintype "passive"))
      (node (ref "TP7") (pin "1") (pintype "passive"))
    )
    (net (code "12") (name "/P1.6") (class "Default")
      (node (ref "TP22") (pin "1") (pintype "passive"))
      (node (ref "U3") (pin "14") (pinfunction "P1.6/TA0.1/A6/CA6/UCB0SOMI/UCB0SCL/TDI/TCLK_14") (pintype "bidirectional"))
    )
    (net (code "13") (name "/P1.7") (class "Default")
      (node (ref "TP23") (pin "1") (pintype "passive"))
      (node (ref "U3") (pin "15") (pinfunction "P1.7/A7/CA7/CAOUT/UCB0SIMO/UCB0SDA/TDO/TDI_15") (pintype "bidirectional"))
    )
    (net (code "14") (name "/P2.0") (class "Default")
      (node (ref "TP20") (pin "1") (pintype "passive"))
      (node (ref "U3") (pin "8") (pinfunction "P2.0/TA1.0_8") (pintype "bidirectional"))
    )
    (net (code "15") (name "/P2.2") (class "Default")
      (node (ref "TP21") (pin "1") (pintype "passive"))
      (node (ref "U3") (pin "10") (pinfunction "P2.2/TA1.1_10") (pintype "bidirectional"))
    )
    (net (code "16") (name "/PH{slash}IN1") (class "Default")
      (node (ref "H12") (pin "8") (pinfunction "8_8") (pintype "passive"))
      (node (ref "R29") (pin "1") (pinfunction "1_1") (pintype "passive"))
      (node (ref "U1") (pin "15") (pinfunction "PH/IN1_15") (pintype "input"))
    )
    (net (code "17") (name "/PH{slash}IN1_MCU") (class "Default")
      (node (ref "R29") (pin "2") (pinfunction "2_2") (pintype "passive"))
      (node (ref "U3") (pin "13") (pinfunction "P2.5/TA1.2_13") (pintype "bidirectional"))
    )
    (net (code "18") (name "/POT") (class "Default")
      (node (ref "R19") (pin "2") (pinfunction "WIPER_2") (pintype "passive"))
      (node (ref "U3") (pin "6") (pinfunction "P1.4/SMCLK/UCB0STE/UCA0CLK/A4/VREF+/VEREF+/CA4/TCK_6") (pintype "bidirectional"))
    )
    (net (code "19") (name "/PUSH") (class "Default")
      (node (ref "J2") (pin "3") (pinfunction "3_3") (pintype "passive"))
      (node (ref "R15") (pin "1") (pinfunction "1_1") (pintype "passive"))
      (node (ref "U3") (pin "5") (pinfunction "P1.3/ADC10CLK/A3/VREF-/VEREF-/CA3/CAOUT_5") (pintype "bidirectional"))
    )
    (net (code "20") (name "/RESET") (class "Default")
      (node (ref "C22") (pin "1") (pinfunction "1_1") (pintype "passive"))
      (node (ref "J2") (pin "1") (pinfunction "1_1") (pintype "passive"))
      (node (ref "J3") (pin "2") (pinfunction "2_2") (pintype "output"))
      (node (ref "R17") (pin "1") (pinfunction "1_1") (pintype "passive"))
      (node (ref "U3") (pin "16") (pinfunction "~{RST}/NMI/SBWTDIO_16") (pintype "input"))
    )
    (net (code "21") (name "/RX") (class "Default")
      (node (ref "U2") (pin "5") (pinfunction "RXD_5") (pintype "input"))
      (node (ref "U3") (pin "4") (pinfunction "P1.2/TA0.1/UCA0TXD/UCA0SIMO/A2/CA2_4") (pintype "output"))
    )
    (net (code "22") (name "/SH1") (class "Default")
      (node (ref "NT2") (pin "1") (pinfunction "1_1") (pintype "passive"))
      (node (ref "U1") (pin "18") (pinfunction "SH1_18") (pintype "input"))
    )
    (net (code "23") (name "/SH2") (class "Default")
      (node (ref "NT1") (pin "1") (pinfunction "1_1") (pintype "passive"))
      (node (ref "U1") (pin "23") (pinfunction "SH2_23") (pintype "input"))
    )
    (net (code "24") (name "/SNSOUT") (class "Default")
      (node (ref "H12") (pin "4") (pinfunction "4_4") (pintype "passive"))
      (node (ref "R16") (pin "1") (pinfunction "1_1") (pintype "passive"))
      (node (ref "R25") (pin "1") (pinfunction "1_1") (pintype "passive"))
      (node (ref "R7") (pin "2") (pinfunction "2_2") (pintype "passive"))
      (node (ref "U1") (pin "10") (pinfunction "SNSOUT_10") (pintype "open_collector"))
    )
    (net (code "25") (name "/SNSOUT_MCU") (class "Default")
      (node (ref "R16") (pin "2") (pinfunction "2_2") (pintype "passive"))
      (node (ref "U3") (pin "18") (pinfunction "P2.7/XOUT_18") (pintype "bidirectional"))
    )
    (net (code "26") (name "/SO") (class "Default")
      (node (ref "H12") (pin "5") (pinfunction "5_5") (pintype "passive"))
      (node (ref "R20") (pin "1") (pinfunction "1_1") (pintype "passive"))
      (node (ref "R30") (pin "1") (pinfunction "1_1") (pintype "passive"))
      (node (ref "R31") (pin "1") (pinfunction "1_1") (pintype "passive"))
    )
    (net (code "27") (name "/SO_MCU") (class "Default")
      (node (ref "R20") (pin "2") (pinfunction "2_2") (pintype "passive"))
      (node (ref "U3") (pin "7") (pinfunction "P1.5/TA0.0/UCB0CLK/UCA0STE/A5/CA5/TMS_7") (pintype "bidirectional"))
    )
    (net (code "28") (name "/STATUS") (class "Default")
      (node (ref "D1") (pin "1") (pinfunction "A_1") (pintype "passive"))
      (node (ref "U3") (pin "2") (pinfunction "P1.0/TA0CLK/ACLK/A0/CA0_2") (pintype "bidirectional"))
    )
    (net (code "29") (name "/S_N") (class "Default")
      (node (ref "C17") (pin "2") (pinfunction "2_2") (pintype "passive"))
      (node (ref "NT4") (pin "1") (pinfunction "1_1") (pintype "passive"))
      (node (ref "U1") (pin "20") (pinfunction "SN_20") (pintype "input"))
    )
    (net (code "30") (name "/S_P") (class "Default")
      (node (ref "C17") (pin "1") (pinfunction "1_1") (pintype "passive"))
      (node (ref "NT3") (pin "2") (pinfunction "2_2") (pintype "passive"))
      (node (ref "U1") (pin "21") (pinfunction "SP_21") (pintype "input"))
    )
    (net (code "31") (name "/TEST") (class "Default")
      (node (ref "J3") (pin "3") (pinfunction "3_3") (pintype "output"))
      (node (ref "U3") (pin "17") (pinfunction "TEST/SBWTCK_17") (pintype "input"))
    )
    (net (code "32") (name "/TX") (class "Default")
      (node (ref "U2") (pin "1") (pinfunction "TXD_1") (pintype "output"))
      (node (ref "U3") (pin "3") (pinfunction "P1.1/TA0.0/UCA0RXD/UCA0SOMI/A1/CA1_3") (pintype "input"))
    )
    (net (code "33") (name "/VCP") (class "Default")
      (node (ref "C9") (pin "1") (pinfunction "1_1") (pintype "passive"))
      (node (ref "TP13") (pin "1") (pintype "passive"))
      (node (ref "U1") (pin "2") (pinfunction "VCP_2") (pintype "power_in"))
    )
    (net (code "34") (name "/VREF") (class "Default")
      (node (ref "H12") (pin "2") (pinfunction "2_2") (pintype "passive"))
      (node (ref "R12") (pin "1") (pinfunction "1_1") (pintype "passive"))
      (node (ref "R6") (pin "1") (pinfunction "1_1") (pintype "passive"))
      (node (ref "R8") (pin "2") (pinfunction "2_2") (pintype "passive"))
      (node (ref "U1") (pin "6") (pinfunction "VREF_6") (pintype "input"))
    )
    (net (code "35") (name "/VREF_MCU") (class "Default")
      (node (ref "C19") (pin "1") (pinfunction "1_1") (pintype "passive"))
      (node (ref "R11") (pin "2") (pinfunction "2_2") (pintype "passive"))
      (node (ref "R12") (pin "2") (pinfunction "2_2") (pintype "passive"))
    )
    (net (code "36") (name "/nFAULT") (class "Default")
      (node (ref "H12") (pin "3") (pinfunction "3_3") (pintype "passive"))
      (node (ref "R14") (pin "1") (pinfunction "1_1") (pintype "passive"))
      (node (ref "R24") (pin "1") (pinfunction "1_1") (pintype "passive"))
      (node (ref "R5") (pin "2") (pinfunction "2_2") (pintype "passive"))
      (node (ref "U1") (pin "9") (pinfunction "FAULT_9") (pintype "open_collector"))
    )
    (net (code "37") (name "/nFAULT_MCU") (class "Default")
      (node (ref "R14") (pin "2") (pinfunction "2_2") (pintype "passive"))
      (node (ref "U3") (pin "11") (pinfunction "P2.3/TA1.0_11") (pintype "bidirectional"))
    )
    (net (code "38") (name "/nSLEEP") (class "Default")
      (node (ref "H12") (pin "6") (pinfunction "6_6") (pintype "passive"))
      (node (ref "R21") (pin "1") (pinfunction "1_1") (pintype "passive"))
      (node (ref "U1") (pin "13") (pinfunction "SLEEP_13") (pintype "input"))
    )
    (net (code "39") (name "/nSLEEP_MCU") (class "Default")
      (node (ref "R21") (pin "2") (pinfunction "2_2") (pintype "passive"))
      (node (ref "U3") (pin "12") (pinfunction "P2.4/TA1.2_12") (pintype "bidirectional"))
    )
    (net (code "40") (name "3.3V") (class "Default")
      (node (ref "D2") (pin "1") (pinfunction "A_1") (pintype "passive"))
      (node (ref "D3") (pin "1") (pinfunction "A_1") (pintype "passive"))
      (node (ref "H12") (pin "1") (pinfunction "1_1") (pintype "passive"))
      (node (ref "R10") (pin "1") (pinfunction "1_1") (pintype "passive"))
      (node (ref "R5") (pin "1") (pinfunction "1_1") (pintype "passive"))
      (node (ref "R7") (pin "1") (pinfunction "1_1") (pintype "passive"))
    )
    (net (code "41") (name "3.3V_MCU") (class "Default")
      (node (ref "C18") (pin "1") (pinfunction "1_1") (pintype "passive"))
      (node (ref "C20") (pin "1") (pinfunction "1_1") (pintype "passive"))
      (node (ref "C21") (pin "1") (pinfunction "1_1") (pintype "passive"))
      (node (ref "R10") (pin "2") (pinfunction "2_2") (pintype "passive"))
      (node (ref "R15") (pin "2") (pinfunction "2_2") (pintype "passive"))
      (node (ref "R17") (pin "2") (pinfunction "2_2") (pintype "passive"))
      (node (ref "R18") (pin "2") (pinfunction "2_2") (pintype "passive"))
      (node (ref "R19") (pin "1") (pinfunction "CCW_1") (pintype "passive"))
      (node (ref "U2") (pin "17") (pinfunction "3V3OUT_17") (pintype "power_in"))
      (node (ref "U2") (pin "4") (pinfunction "VCCIO_4") (pintype "power_in"))
      (node (ref "U3") (pin "1") (pinfunction "DVCC_1") (pintype "power_in"))
    )
    (net (code "42") (name "5V_USB") (class "Default")
      (node (ref "C3") (pin "1") (pinfunction "1_1") (pintype "passive"))
      (node (ref "C4") (pin "1") (pinfunction "1_1") (pintype "passive"))
      (node (ref "F1") (pin "2") (pintype "passive"))
      (node (ref "U2") (pin "20") (pinfunction "VCC_20") (pintype "power_in"))
    )
    (net (code "43") (name "AVDD") (class "Default")
      (node (ref "C15") (pin "1") (pinfunction "1_1") (pintype "passive"))
      (node (ref "J1") (pin "1") (pinfunction "1_1") (pintype "passive"))
      (node (ref "R13") (pin "2") (pinfunction "2_2") (pintype "passive"))
      (node (ref "R6") (pin "2") (pinfunction "2_2") (pintype "passive"))
      (node (ref "TP15") (pin "1") (pintype "passive"))
      (node (ref "U1") (pin "7") (pinfunction "AVDD_7") (pintype "power_in"))
    )
    (net (code "44") (name "DVDD") (class "Default")
      (node (ref "C16") (pin "2") (pinfunction "2_2") (pintype "passive"))
      (node (ref "TP16") (pin "1") (pintype "passive"))
      (node (ref "U1") (pin "8") (pinfunction "DVDD_8") (pintype "power_in"))
    )
    (net (code "45") (name "GND") (class "Default")
      (node (ref "C1") (pin "2") (pinfunction "-_2") (pintype "passive"))
      (node (ref "C10") (pin "2") (pinfunction "2_2") (pintype "passive"))
      (node (ref "C11") (pin "2") (pinfunction "2_2") (pintype "passive"))
      (node (ref "C15") (pin "2") (pinfunction "2_2") (pintype "passive"))
      (node (ref "C16") (pin "1") (pinfunction "1_1") (pintype "passive"))
      (node (ref "C18") (pin "2") (pinfunction "2_2") (pintype "passive"))
      (node (ref "C19") (pin "2") (pinfunction "2_2") (pintype "passive"))
      (node (ref "C2") (pin "2") (pinfunction "-_2") (pintype "passive"))
      (node (ref "C20") (pin "2") (pinfunction "2_2") (pintype "passive"))
      (node (ref "C21") (pin "2") (pinfunction "2_2") (pintype "passive"))
      (node (ref "C22") (pin "2") (pinfunction "2_2") (pintype "passive"))
      (node (ref "C3") (pin "2") (pinfunction "2_2") (pintype "passive"))
      (node (ref "C4") (pin "2") (pinfunction "2_2") (pintype "passive"))
      (node (ref "C5") (pin "2") (pinfunction "2_2") (pintype "passive"))
      (node (ref "C6") (pin "2") (pinfunction "2_2") (pintype "passive"))
      (node (ref "H10") (pin "2") (pinfunction "2_2") (pintype "passive"))
      (node (ref "H12") (pin "10") (pinfunction "10_10") (pintype "passive"))
      (node (ref "H12") (pin "9") (pinfunction "9_9") (pintype "passive"))
      (node (ref "H9") (pin "10") (pinfunction "10_10") (pintype "passive"))
      (node (ref "H9") (pin "11") (pinfunction "11_11") (pintype "passive"))
      (node (ref "H9") (pin "5") (pinfunction "5_5") (pintype "passive"))
      (node (ref "H9") (pin "6") (pinfunction "6_6") (pintype "passive"))
      (node (ref "H9") (pin "7") (pinfunction "7_7") (pintype "passive"))
      (node (ref "H9") (pin "8") (pinfunction "8_8") (pintype "passive"))
      (node (ref "H9") (pin "9") (pinfunction "9_9") (pintype "passive"))
      (node (ref "J1") (pin "11") (pinfunction "11_11") (pintype "passive"))
      (node (ref "J3") (pin "1") (pinfunction "1_1") (pintype "power_in"))
      (node (ref "NT4") (pin "2") (pinfunction "2_2") (pintype "passive"))
      (node (ref "R19") (pin "3") (pinfunction "CW_3") (pintype "passive"))
      (node (ref "R23") (pin "1") (pinfunction "1_1") (pintype "passive"))
      (node (ref "R26") (pin "1") (pinfunction "1_1") (pintype "passive"))
      (node (ref "R27") (pin "1") (pinfunction "1_1") (pintype "passive"))
      (node (ref "R28") (pin "1") (pinfunction "1_1") (pintype "passive"))
      (node (ref "R31") (pin "2") (pinfunction "2_2") (pintype "passive"))
      (node (ref "R8") (pin "1") (pinfunction "1_1") (pintype "passive"))
      (node (ref "R9") (pin "1") (pinfunction "1_1") (pintype "passive"))
      (node (ref "S1") (pin "3") (pinfunction "3_3") (pintype "passive"))
      (node (ref "S1") (pin "4") (pinfunction "4_4") (pintype "passive"))
      (node (ref "TP14") (pin "1") (pinfunction "1_1") (pintype "passive"))
      (node (ref "TP14") (pin "2") (pinfunction "2_2") (pintype "passive"))
      (node (ref "TP19") (pin "1") (pintype "passive"))
      (node (ref "TP4") (pin "1") (pintype "passive"))
      (node (ref "U1") (pin "16") (pinfunction "GND_16") (pintype "power_in"))
      (node (ref "U1") (pin "25") (pinfunction "PAD_25") (pintype "power_in"))
      (node (ref "U1") (pin "5") (pinfunction "GND_5") (pintype "power_in"))
      (node (ref "U2") (pin "18") (pinfunction "GND_18") (pintype "power_in"))
      (node (ref "U2") (pin "21") (pinfunction "GND_21") (pintype "power_in"))
      (node (ref "U2") (pin "25") (pinfunction "AGND_25") (pintype "power_in"))
      (node (ref "U2") (pin "26") (pinfunction "TEST_26") (pintype "input"))
      (node (ref "U2") (pin "7") (pinfunction "GND_7") (pintype "power_in"))
      (node (ref "U3") (pin "20") (pinfunction "DVSS_20") (pintype "power_in"))
    )
    (net (code "46") (name "Net-(C13-Pad2)") (class "Default")
      (node (ref "C13") (pin "2") (pinfunction "2_2") (pintype "passive"))
      (node (ref "C14") (pin "2") (pinfunction "2_2") (pintype "passive"))
      (node (ref "NT3") (pin "1") (pinfunction "1_1") (pintype "passive"))
      (node (ref "Q3") (pin "1") (pinfunction "S_1") (pintype "passive"))
      (node (ref "Q3") (pin "2") (pinfunction "S_2") (pintype "passive"))
      (node (ref "Q3") (pin "3") (pinfunction "S_3") (pintype "passive"))
      (node (ref "Q4") (pin "1") (pinfunction "S_1") (pintype "passive"))
      (node (ref "Q4") (pin "2") (pinfunction "S_2") (pintype "passive"))
      (node (ref "Q4") (pin "3") (pinfunction "S_3") (pintype "passive"))
      (node (ref "R9") (pin "2") (pinfunction "2_2") (pintype "passive"))
      (node (ref "TP12") (pin "1") (pintype "passive"))
    )
    (net (code "47") (name "Net-(D1-K)") (class "Default")
      (node (ref "D1") (pin "2") (pinfunction "K_2") (pintype "passive"))
      (node (ref "R23") (pin "2") (pinfunction "2_2") (pintype "passive"))
    )
    (net (code "48") (name "Net-(D2-K)") (class "Default")
      (node (ref "D2") (pin "2") (pinfunction "K_2") (pintype "passive"))
      (node (ref "R24") (pin "2") (pinfunction "2_2") (pintype "passive"))
    )
    (net (code "49") (name "Net-(D3-K)") (class "Default")
      (node (ref "D3") (pin "2") (pinfunction "K_2") (pintype "passive"))
      (node (ref "R25") (pin "2") (pinfunction "2_2") (pintype "passive"))
    )
    (net (code "50") (name "Net-(D4-K)") (class "Default")
      (node (ref "D4") (pin "2") (pinfunction "K_2") (pintype "passive"))
      (node (ref "R26") (pin "2") (pinfunction "2_2") (pintype "passive"))
    )
    (net (code "51") (name "Net-(F1-Pad1)") (class "Default")
      (node (ref "F1") (pin "1") (pintype "passive"))
      (node (ref "H9") (pin "1") (pinfunction "1_1") (pintype "passive"))
    )
    (net (code "52") (name "Net-(J1-Pad3)") (class "Default")
      (node (ref "J1") (pin "3") (pinfunction "3_3") (pintype "passive"))
      (node (ref "R13") (pin "1") (pinfunction "1_1") (pintype "passive"))
    )
    (net (code "53") (name "Net-(J1-Pad7)") (class "Default")
      (node (ref "J1") (pin "7") (pinfunction "7_7") (pintype "passive"))
      (node (ref "R27") (pin "2") (pinfunction "2_2") (pintype "passive"))
    )
    (net (code "54") (name "Net-(J1-Pad9)") (class "Default")
      (node (ref "J1") (pin "9") (pinfunction "9_9") (pintype "passive"))
      (node (ref "R28") (pin "2") (pinfunction "2_2") (pintype "passive"))
    )
    (net (code "55") (name "Net-(J2-Pad2)") (class "Default")
      (node (ref "J2") (pin "2") (pinfunction "2_2") (pintype "passive"))
      (node (ref "S1") (pin "1") (pinfunction "1_1") (pintype "passive"))
      (node (ref "S1") (pin "2") (pinfunction "2_2") (pintype "passive"))
    )
    (net (code "56") (name "Net-(J3-Pad4)") (class "Default")
      (node (ref "J3") (pin "4") (pinfunction "4_4") (pintype "power_in"))
      (node (ref "R18") (pin "1") (pinfunction "1_1") (pintype "passive"))
    )
    (net (code "57") (name "Net-(Q1-G)") (class "Default")
      (node (ref "Q1") (pin "4") (pinfunction "G_4") (pintype "passive"))
      (node (ref "R1") (pin "1") (pinfunction "1_1") (pintype "passive"))
      (node (ref "TP5") (pin "1") (pintype "passive"))
    )
    (net (code "58") (name "Net-(Q2-G)") (class "Default")
      (node (ref "Q2") (pin "4") (pinfunction "G_4") (pintype "passive"))
      (node (ref "R2") (pin "2") (pinfunction "2_2") (pintype "passive"))
      (node (ref "TP6") (pin "1") (pintype "passive"))
    )
    (net (code "59") (name "Net-(Q3-G)") (class "Default")
      (node (ref "Q3") (pin "4") (pinfunction "G_4") (pintype "passive"))
      (node (ref "R3") (pin "1") (pinfunction "1_1") (pintype "passive"))
      (node (ref "TP9") (pin "1") (pintype "passive"))
    )
    (net (code "60") (name "Net-(Q4-G)") (class "Default")
      (node (ref "Q4") (pin "4") (pinfunction "G_4") (pintype "passive"))
      (node (ref "R4") (pin "2") (pinfunction "2_2") (pintype "passive"))
      (node (ref "TP10") (pin "1") (pintype "passive"))
    )
    (net (code "61") (name "Net-(U1-CPH)") (class "Default")
      (node (ref "C12") (pin "1") (pinfunction "1_1") (pintype "passive"))
      (node (ref "U1") (pin "3") (pinfunction "CPH_3") (pintype "passive"))
    )
    (net (code "62") (name "Net-(U1-CPL)") (class "Default")
      (node (ref "C12") (pin "2") (pinfunction "2_2") (pintype "passive"))
      (node (ref "U1") (pin "4") (pinfunction "CPL_4") (pintype "passive"))
    )
    (net (code "63") (name "Net-(U1-SO)") (class "Default")
      (node (ref "R30") (pin "2") (pinfunction "2_2") (pintype "passive"))
      (node (ref "U1") (pin "11") (pinfunction "SO_11") (pintype "output"))
    )
    (net (code "64") (name "Net-(U3-P2.6{slash}XIN{slash}TA0.1)") (class "Default")
      (node (ref "R11") (pin "1") (pinfunction "1_1") (pintype "passive"))
      (node (ref "U3") (pin "19") (pinfunction "P2.6/XIN/TA0.1_19") (pintype "bidirectional"))
    )
    (net (code "65") (name "VM") (class "Default")
      (node (ref "C1") (pin "1") (pinfunction "+_1") (pintype "passive"))
      (node (ref "C10") (pin "1") (pinfunction "1_1") (pintype "passive"))
      (node (ref "C11") (pin "1") (pinfunction "1_1") (pintype "passive"))
      (node (ref "C2") (pin "1") (pinfunction "+_1") (pintype "passive"))
      (node (ref "C5") (pin "1") (pinfunction "1_1") (pintype "passive"))
      (node (ref "C6") (pin "1") (pinfunction "1_1") (pintype "passive"))
      (node (ref "C7") (pin "1") (pinfunction "1_1") (pintype "passive"))
      (node (ref "C8") (pin "1") (pinfunction "1_1") (pintype "passive"))
      (node (ref "C9") (pin "2") (pinfunction "2_2") (pintype "passive"))
      (node (ref "D4") (pin "1") (pinfunction "A_1") (pintype "passive"))
      (node (ref "H10") (pin "1") (pinfunction "1_1") (pintype "passive"))
      (node (ref "Q1") (pin "5") (pinfunction "D_5") (pintype "passive"))
      (node (ref "Q1") (pin "6") (pinfunction "D_6") (pintype "passive"))
      (node (ref "Q1") (pin "7") (pinfunction "D_7") (pintype "passive"))
      (node (ref "Q1") (pin "8") (pinfunction "D_8") (pintype "passive"))
      (node (ref "Q2") (pin "5") (pinfunction "D_5") (pintype "passive"))
      (node (ref "Q2") (pin "6") (pinfunction "D_6") (pintype "passive"))
      (node (ref "Q2") (pin "7") (pinfunction "D_7") (pintype "passive"))
      (node (ref "Q2") (pin "8") (pinfunction "D_8") (pintype "passive"))
      (node (ref "TP1") (pin "1") (pintype "passive"))
      (node (ref "TP11") (pin "1") (pintype "passive"))
      (node (ref "TP2") (pin "1") (pintype "passive"))
      (node (ref "TP3") (pin "1") (pintype "passive"))
      (node (ref "U1") (pin "1") (pinfunction "VM_1") (pintype "power_in"))
    )
    (net (code "66") (name "unconnected-(H9-Pad4)") (class "Default")
      (node (ref "H9") (pin "4") (pinfunction "4_4") (pintype "passive+no_connect"))
    )
    (net (code "67") (name "unconnected-(J1-Pad5)") (class "Default")
      (node (ref "J1") (pin "5") (pinfunction "5_5") (pintype "passive+no_connect"))
    )
    (net (code "68") (name "unconnected-(U2-CBUS0-Pad23)") (class "Default")
      (node (ref "U2") (pin "23") (pinfunction "CBUS0_23") (pintype "bidirectional+no_connect"))
    )
    (net (code "69") (name "unconnected-(U2-CBUS1-Pad22)") (class "Default")
      (node (ref "U2") (pin "22") (pinfunction "CBUS1_22") (pintype "bidirectional+no_connect"))
    )
    (net (code "70") (name "unconnected-(U2-CBUS2-Pad13)") (class "Default")
      (node (ref "U2") (pin "13") (pinfunction "CBUS2_13") (pintype "bidirectional+no_connect"))
    )
    (net (code "71") (name "unconnected-(U2-CBUS3-Pad14)") (class "Default")
      (node (ref "U2") (pin "14") (pinfunction "CBUS3_14") (pintype "bidirectional+no_connect"))
    )
    (net (code "72") (name "unconnected-(U2-CBUS4-Pad12)") (class "Default")
      (node (ref "U2") (pin "12") (pinfunction "CBUS4_12") (pintype "bidirectional+no_connect"))
    )
    (net (code "73") (name "unconnected-(U2-CTS-Pad11)") (class "Default")
      (node (ref "U2") (pin "11") (pinfunction "CTS_11") (pintype "input+no_connect"))
    )
    (net (code "74") (name "unconnected-(U2-DCD-Pad10)") (class "Default")
      (node (ref "U2") (pin "10") (pinfunction "DCD_10") (pintype "input+no_connect"))
    )
    (net (code "75") (name "unconnected-(U2-DSR-Pad9)") (class "Default")
      (node (ref "U2") (pin "9") (pinfunction "DSR_9") (pintype "input+no_connect"))
    )
    (net (code "76") (name "unconnected-(U2-DTR-Pad2)") (class "Default")
      (node (ref "U2") (pin "2") (pinfunction "DTR_2") (pintype "output+no_connect"))
    )
    (net (code "77") (name "unconnected-(U2-NC-Pad8)") (class "Default")
      (node (ref "U2") (pin "8") (pinfunction "NC_8") (pintype "passive+no_connect"))
    )
    (net (code "78") (name "unconnected-(U2-NC-Pad24)") (class "Default")
      (node (ref "U2") (pin "24") (pinfunction "NC_24") (pintype "passive+no_connect"))
    )
    (net (code "79") (name "unconnected-(U2-OSCI-Pad27)") (class "Default")
      (node (ref "U2") (pin "27") (pinfunction "OSCI_27") (pintype "passive+no_connect"))
    )
    (net (code "80") (name "unconnected-(U2-OSCO-Pad28)") (class "Default")
      (node (ref "U2") (pin "28") (pinfunction "OSCO_28") (pintype "output+no_connect"))
    )
    (net (code "81") (name "unconnected-(U2-RESET-Pad19)") (class "Default")
      (node (ref "U2") (pin "19") (pinfunction "RESET_19") (pintype "input+no_connect"))
    )
    (net (code "82") (name "unconnected-(U2-RI-Pad6)") (class "Default")
      (node (ref "U2") (pin "6") (pinfunction "RI_6") (pintype "input+no_connect"))
    )
    (net (code "83") (name "unconnected-(U2-RTS-Pad3)") (class "Default")
      (node (ref "U2") (pin "3") (pinfunction "RTS_3") (pintype "output+no_connect"))
    )
  )
)
